# TRV_WIZ.net
KiCad netlist of a schematic drawn in EAGLE
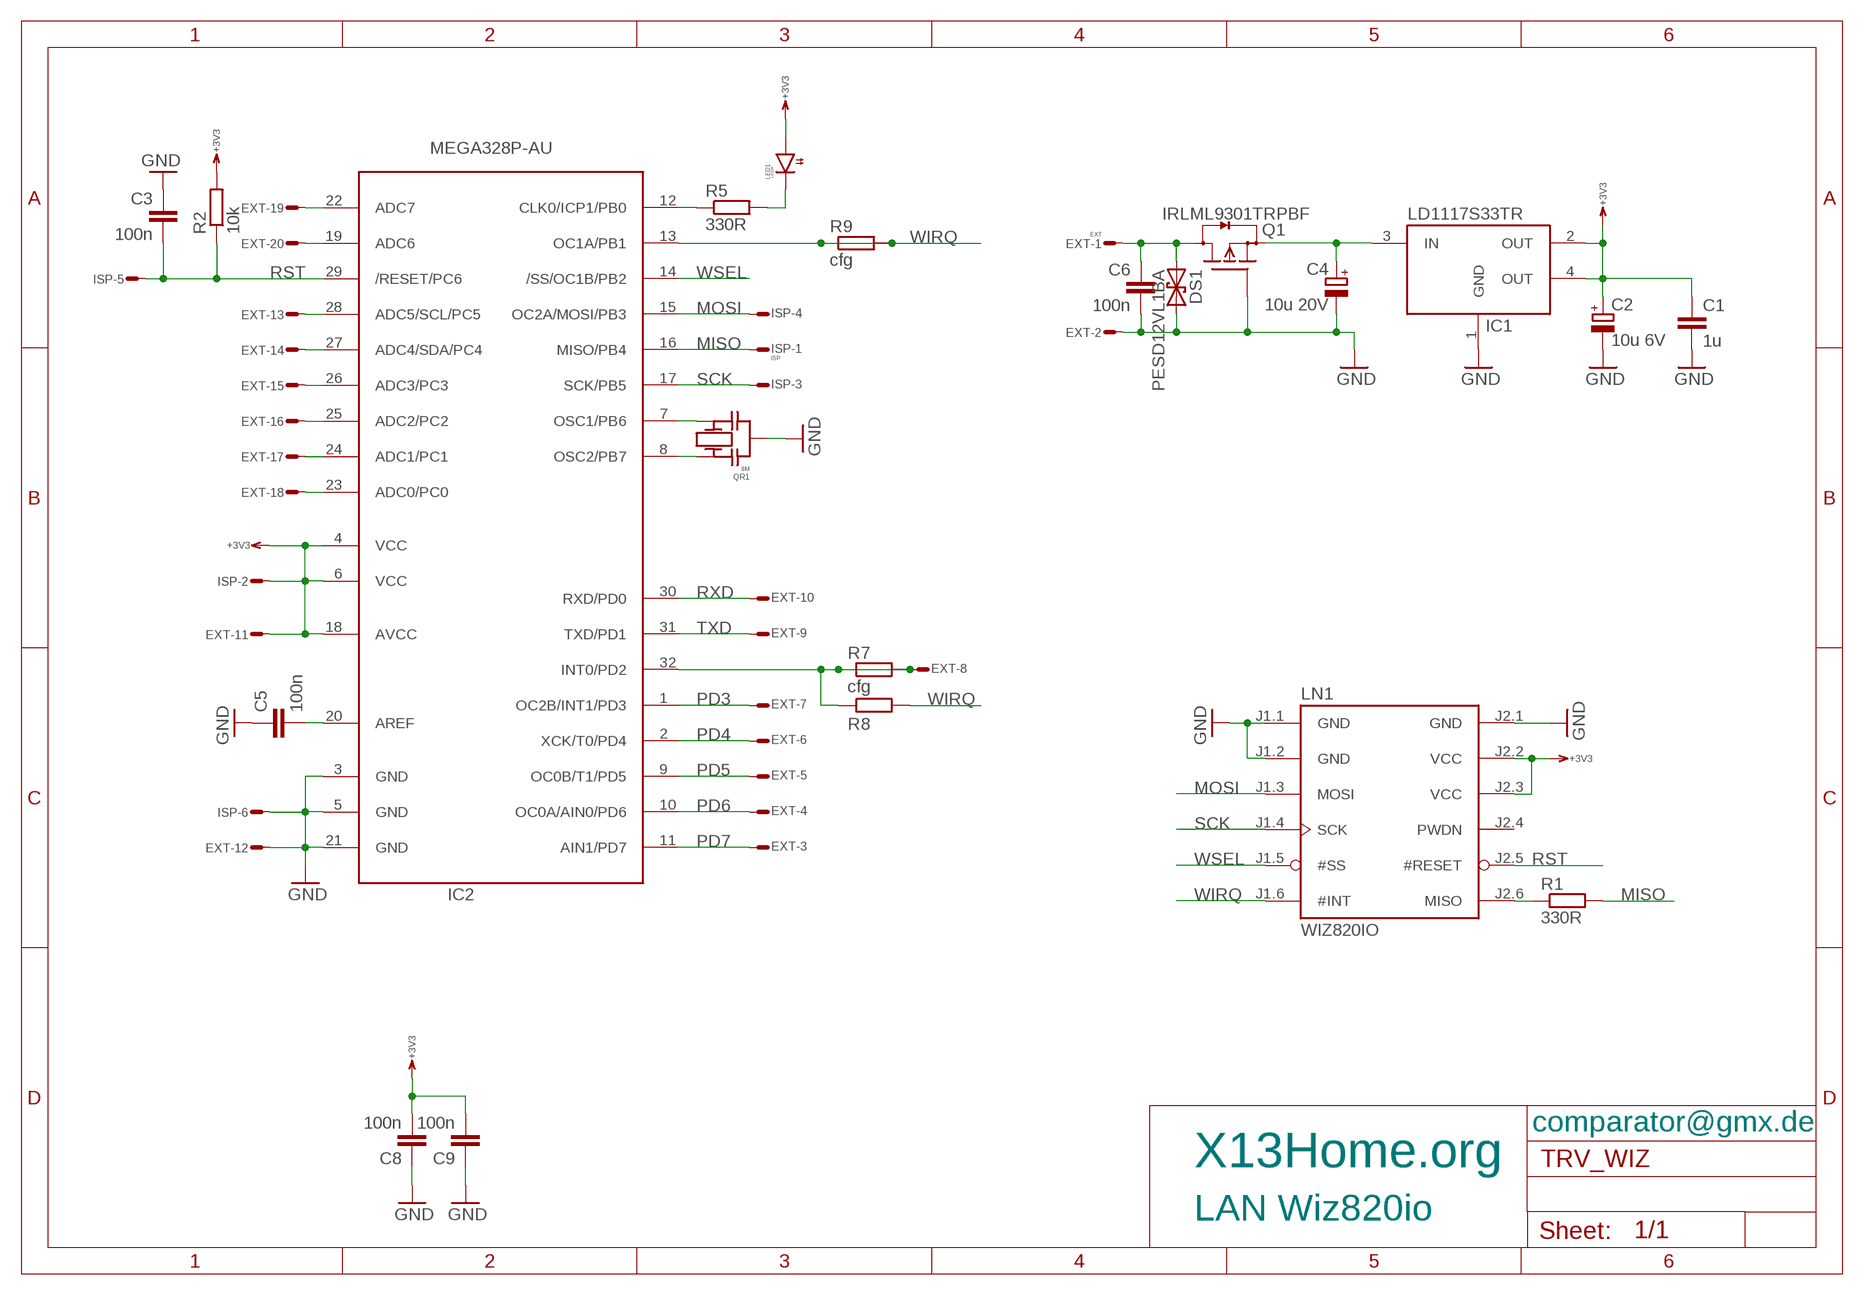
[diagram p0: schematic, sheet 1]

(export (version "E")
  (design (tool "Eeschema 10.0.6"))
  (components
    (comp (ref "C1")
      (value "1u")
      (footprint "eagle-import:0603")
      (libsource (lib "eagle-import") (part "C0603"))
    )
    (comp (ref "C2")
      (value "10u 6V")
      (footprint "eagle-import:SMC_A")
      (libsource (lib "eagle-import") (part "C_POLSMCA"))
    )
    (comp (ref "C3")
      (value "100n")
      (footprint "eagle-import:0603")
      (libsource (lib "eagle-import") (part "C0603"))
    )
    (comp (ref "C4")
      (value "10u 20V")
      (footprint "eagle-import:SMC_B")
      (libsource (lib "eagle-import") (part "C_POLSMCB"))
    )
    (comp (ref "C5")
      (value "100n")
      (footprint "eagle-import:0603")
      (libsource (lib "eagle-import") (part "C0603"))
    )
    (comp (ref "C6")
      (value "100n")
      (footprint "eagle-import:0603")
      (libsource (lib "eagle-import") (part "C0603"))
    )
    (comp (ref "C8")
      (value "100n")
      (footprint "eagle-import:0603")
      (libsource (lib "eagle-import") (part "C0603"))
    )
    (comp (ref "C9")
      (value "100n")
      (footprint "eagle-import:0603")
      (libsource (lib "eagle-import") (part "C0603"))
    )
    (comp (ref "DS1")
      (value "PESD12VL1BA")
      (footprint "eagle-import:SOD323")
      (libsource (lib "eagle-import") (part "TVS-U323"))
    )
    (comp (ref "EXT")
      (value "EXT")
      (footprint "eagle-import:ML20S")
      (libsource (lib "eagle-import") (part "ML20?ES"))
    )
    (comp (ref "IC1")
      (value "LD1117S33TR")
      (footprint "eagle-import:SOT223")
      (libsource (lib "eagle-import") (part "LDO_4P"))
    )
    (comp (ref "IC2")
      (value "MEGA328P-AU")
      (footprint "eagle-import:TQFP32-08")
      (libsource (lib "eagle-import") (part "MEGA168PA"))
    )
    (comp (ref "ISP")
      (value "ISP")
      (footprint "eagle-import:ML6S")
      (libsource (lib "eagle-import") (part "ML6ES"))
    )
    (comp (ref "LED1")
      (value "LEDR")
      (footprint "eagle-import:T1-3_4")
      (libsource (lib "eagle-import") (part "LEDT134"))
    )
    (comp (ref "LN1")
      (value "WIZ820IO")
      (footprint "eagle-import:WIZ820IO")
      (libsource (lib "eagle-import") (part "WIZ820IO"))
    )
    (comp (ref "Q1")
      (value "IRLML9301TRPBF")
      (footprint "eagle-import:SOT23")
      (libsource (lib "eagle-import") (part "FET-PDSOT23"))
    )
    (comp (ref "QR1")
      (value "8M")
      (footprint "eagle-import:CSTCE")
      (libsource (lib "eagle-import") (part "QRCE"))
    )
    (comp (ref "R1")
      (value "330R")
      (footprint "eagle-import:0603")
      (libsource (lib "eagle-import") (part "R0603"))
    )
    (comp (ref "R2")
      (value "10k")
      (footprint "eagle-import:0603")
      (libsource (lib "eagle-import") (part "R0603"))
    )
    (comp (ref "R5")
      (value "330R")
      (footprint "eagle-import:0603")
      (libsource (lib "eagle-import") (part "R0603"))
    )
    (comp (ref "R7")
      (value "cfg")
      (footprint "eagle-import:0402")
      (libsource (lib "eagle-import") (part "R0402"))
    )
    (comp (ref "R8")
      (value "cfg")
      (footprint "eagle-import:0402")
      (libsource (lib "eagle-import") (part "R0402"))
    )
    (comp (ref "R9")
      (value "cfg")
      (footprint "eagle-import:0402")
      (libsource (lib "eagle-import") (part "R0402"))
    )
  )
  (nets
    (net (code "1") (name "+3V3") (class "Default")
      (node (ref "C1") (pin "1") (pinfunction "1_1") (pintype "passive"))
      (node (ref "C2") (pin "+") (pinfunction "+_+") (pintype "passive"))
      (node (ref "C8") (pin "2") (pinfunction "2_2") (pintype "passive"))
      (node (ref "C9") (pin "2") (pinfunction "2_2") (pintype "passive"))
      (node (ref "EXT") (pin "11") (pinfunction "S_11") (pintype "passive"))
      (node (ref "IC1") (pin "2") (pinfunction "OUT_2") (pintype "bidirectional"))
      (node (ref "IC1") (pin "4") (pinfunction "OUT_4") (pintype "bidirectional"))
      (node (ref "IC2") (pin "18") (pinfunction "AVCC_18") (pintype "bidirectional"))
      (node (ref "IC2") (pin "4") (pinfunction "VCC_4") (pintype "bidirectional"))
      (node (ref "IC2") (pin "6") (pinfunction "VCC_6") (pintype "bidirectional"))
      (node (ref "ISP") (pin "2") (pinfunction "S_2") (pintype "passive"))
      (node (ref "LED1") (pin "A") (pinfunction "A_A") (pintype "bidirectional"))
      (node (ref "LN1") (pin "J2.2") (pinfunction "VCC_J2.2") (pintype "bidirectional"))
      (node (ref "LN1") (pin "J2.3") (pinfunction "VCC_J2.3") (pintype "bidirectional"))
      (node (ref "R2") (pin "2") (pinfunction "2_2") (pintype "passive"))
    )
    (net (code "2") (name "/MISO") (class "Default")
      (node (ref "IC2") (pin "16") (pinfunction "MISO/PB4_16") (pintype "bidirectional"))
      (node (ref "ISP") (pin "1") (pinfunction "S_1") (pintype "passive"))
      (node (ref "R1") (pin "2") (pinfunction "2_2") (pintype "passive"))
    )
    (net (code "3") (name "/MOSI") (class "Default")
      (node (ref "IC2") (pin "15") (pinfunction "OC2A/MOSI/PB3_15") (pintype "bidirectional"))
      (node (ref "ISP") (pin "4") (pinfunction "S_4") (pintype "passive"))
      (node (ref "LN1") (pin "J1.3") (pinfunction "MOSI_J1.3") (pintype "input"))
    )
    (net (code "4") (name "/PD3") (class "Default")
      (node (ref "EXT") (pin "7") (pinfunction "S_7") (pintype "passive"))
      (node (ref "IC2") (pin "1") (pinfunction "OC2B/INT1/PD3_1") (pintype "bidirectional"))
    )
    (net (code "5") (name "/PD4") (class "Default")
      (node (ref "EXT") (pin "6") (pinfunction "S_6") (pintype "passive"))
      (node (ref "IC2") (pin "2") (pinfunction "XCK/T0/PD4_2") (pintype "bidirectional"))
    )
    (net (code "6") (name "/PD5") (class "Default")
      (node (ref "EXT") (pin "5") (pinfunction "S_5") (pintype "passive"))
      (node (ref "IC2") (pin "9") (pinfunction "OC0B/T1/PD5_9") (pintype "bidirectional"))
    )
    (net (code "7") (name "/PD6") (class "Default")
      (node (ref "EXT") (pin "4") (pinfunction "S_4") (pintype "passive"))
      (node (ref "IC2") (pin "10") (pinfunction "OC0A/AIN0/PD6_10") (pintype "bidirectional"))
    )
    (net (code "8") (name "/PD7") (class "Default")
      (node (ref "EXT") (pin "3") (pinfunction "S_3") (pintype "passive"))
      (node (ref "IC2") (pin "11") (pinfunction "AIN1/PD7_11") (pintype "bidirectional"))
    )
    (net (code "9") (name "/RST") (class "Default")
      (node (ref "C3") (pin "2") (pinfunction "2_2") (pintype "passive"))
      (node (ref "IC2") (pin "29") (pinfunction "/RESET/PC6_29") (pintype "bidirectional"))
      (node (ref "ISP") (pin "5") (pinfunction "S_5") (pintype "passive"))
      (node (ref "LN1") (pin "J2.5") (pinfunction "#RESET_J2.5") (pintype "input"))
      (node (ref "R2") (pin "1") (pinfunction "1_1") (pintype "passive"))
    )
    (net (code "10") (name "/RXD") (class "Default")
      (node (ref "EXT") (pin "10") (pinfunction "S_10") (pintype "passive"))
      (node (ref "IC2") (pin "30") (pinfunction "RXD/PD0_30") (pintype "bidirectional"))
    )
    (net (code "11") (name "/SCK") (class "Default")
      (node (ref "IC2") (pin "17") (pinfunction "SCK/PB5_17") (pintype "bidirectional"))
      (node (ref "ISP") (pin "3") (pinfunction "S_3") (pintype "passive"))
      (node (ref "LN1") (pin "J1.4") (pinfunction "SCK_J1.4") (pintype "input"))
    )
    (net (code "12") (name "/TXD") (class "Default")
      (node (ref "EXT") (pin "9") (pinfunction "S_9") (pintype "passive"))
      (node (ref "IC2") (pin "31") (pinfunction "TXD/PD1_31") (pintype "bidirectional"))
    )
    (net (code "13") (name "/WIRQ") (class "Default")
      (node (ref "IC2") (pin "13") (pinfunction "OC1A/PB1_13") (pintype "bidirectional"))
      (node (ref "LN1") (pin "J1.6") (pinfunction "#INT_J1.6") (pintype "open_collector"))
      (node (ref "R8") (pin "2") (pinfunction "2_2") (pintype "passive"))
      (node (ref "R9") (pin "1") (pinfunction "1_1") (pintype "passive"))
      (node (ref "R9") (pin "2") (pinfunction "2_2") (pintype "passive"))
    )
    (net (code "14") (name "/WSEL") (class "Default")
      (node (ref "IC2") (pin "14") (pinfunction "/SS/OC1B/PB2_14") (pintype "bidirectional"))
      (node (ref "LN1") (pin "J1.5") (pinfunction "#SS_J1.5") (pintype "input"))
    )
    (net (code "15") (name "GND") (class "Default")
      (node (ref "C1") (pin "2") (pinfunction "2_2") (pintype "passive"))
      (node (ref "C2") (pin "-") (pinfunction "-_-") (pintype "passive"))
      (node (ref "C3") (pin "1") (pinfunction "1_1") (pintype "passive"))
      (node (ref "C4") (pin "-") (pinfunction "-_-") (pintype "passive"))
      (node (ref "C5") (pin "1") (pinfunction "1_1") (pintype "passive"))
      (node (ref "C6") (pin "2") (pinfunction "2_2") (pintype "passive"))
      (node (ref "C8") (pin "1") (pinfunction "1_1") (pintype "passive"))
      (node (ref "C9") (pin "1") (pinfunction "1_1") (pintype "passive"))
      (node (ref "DS1") (pin "C") (pinfunction "2_C") (pintype "passive"))
      (node (ref "EXT") (pin "12") (pinfunction "S_12") (pintype "passive"))
      (node (ref "EXT") (pin "2") (pinfunction "S_2") (pintype "passive"))
      (node (ref "IC1") (pin "1") (pinfunction "GND_1") (pintype "bidirectional"))
      (node (ref "IC2") (pin "21") (pinfunction "GND_21") (pintype "bidirectional"))
      (node (ref "IC2") (pin "3") (pinfunction "GND_3") (pintype "bidirectional"))
      (node (ref "IC2") (pin "5") (pinfunction "GND_5") (pintype "bidirectional"))
      (node (ref "ISP") (pin "6") (pinfunction "S_6") (pintype "passive"))
      (node (ref "LN1") (pin "J1.1") (pinfunction "GND_J1.1") (pintype "bidirectional"))
      (node (ref "LN1") (pin "J1.2") (pinfunction "GND_J1.2") (pintype "bidirectional"))
      (node (ref "LN1") (pin "J2.1") (pinfunction "GND_J2.1") (pintype "bidirectional"))
      (node (ref "Q1") (pin "1") (pinfunction "G_1") (pintype "passive"))
      (node (ref "QR1") (pin "G") (pinfunction "M_G") (pintype "passive"))
    )
    (net (code "16") (name "Net-(DS1-1)") (class "Default")
      (node (ref "C6") (pin "1") (pinfunction "1_1") (pintype "passive"))
      (node (ref "DS1") (pin "A") (pinfunction "1_A") (pintype "passive"))
      (node (ref "EXT") (pin "1") (pinfunction "S_1") (pintype "passive"))
      (node (ref "Q1") (pin "3") (pinfunction "D_3") (pintype "passive"))
    )
    (net (code "17") (name "Net-(EXTE-S)") (class "Default")
      (node (ref "EXT") (pin "13") (pinfunction "S_13") (pintype "passive"))
      (node (ref "IC2") (pin "28") (pinfunction "ADC5/SCL/PC5_28") (pintype "bidirectional"))
    )
    (net (code "18") (name "Net-(EXTF-S)") (class "Default")
      (node (ref "EXT") (pin "14") (pinfunction "S_14") (pintype "passive"))
      (node (ref "IC2") (pin "27") (pinfunction "ADC4/SDA/PC4_27") (pintype "bidirectional"))
    )
    (net (code "19") (name "Net-(EXTG-S)") (class "Default")
      (node (ref "EXT") (pin "15") (pinfunction "S_15") (pintype "passive"))
      (node (ref "IC2") (pin "26") (pinfunction "ADC3/PC3_26") (pintype "bidirectional"))
    )
    (net (code "20") (name "Net-(EXTH-S)") (class "Default")
      (node (ref "EXT") (pin "16") (pinfunction "S_16") (pintype "passive"))
      (node (ref "IC2") (pin "25") (pinfunction "ADC2/PC2_25") (pintype "bidirectional"))
    )
    (net (code "21") (name "Net-(EXTI-S)") (class "Default")
      (node (ref "EXT") (pin "17") (pinfunction "S_17") (pintype "passive"))
      (node (ref "IC2") (pin "24") (pinfunction "ADC1/PC1_24") (pintype "bidirectional"))
    )
    (net (code "22") (name "Net-(EXTJ-S)") (class "Default")
      (node (ref "EXT") (pin "18") (pinfunction "S_18") (pintype "passive"))
      (node (ref "IC2") (pin "23") (pinfunction "ADC0/PC0_23") (pintype "bidirectional"))
    )
    (net (code "23") (name "Net-(EXTK-S)") (class "Default")
      (node (ref "EXT") (pin "19") (pinfunction "S_19") (pintype "passive"))
      (node (ref "IC2") (pin "22") (pinfunction "ADC7_22") (pintype "bidirectional"))
    )
    (net (code "24") (name "Net-(EXTM-S)") (class "Default")
      (node (ref "EXT") (pin "20") (pinfunction "S_20") (pintype "passive"))
      (node (ref "IC2") (pin "19") (pinfunction "ADC6_19") (pintype "bidirectional"))
    )
    (net (code "25") (name "Net-(EXTS-S)") (class "Default")
      (node (ref "EXT") (pin "8") (pinfunction "S_8") (pintype "passive"))
      (node (ref "IC2") (pin "32") (pinfunction "INT0/PD2_32") (pintype "bidirectional"))
      (node (ref "R7") (pin "1") (pinfunction "1_1") (pintype "passive"))
      (node (ref "R7") (pin "2") (pinfunction "2_2") (pintype "passive"))
      (node (ref "R8") (pin "1") (pinfunction "1_1") (pintype "passive"))
    )
    (net (code "26") (name "Net-(IC1-IN)") (class "Default")
      (node (ref "C4") (pin "+") (pinfunction "+_+") (pintype "passive"))
      (node (ref "IC1") (pin "3") (pinfunction "IN_3") (pintype "bidirectional"))
      (node (ref "Q1") (pin "2") (pinfunction "S_2") (pintype "passive"))
    )
    (net (code "27") (name "Net-(IC2-AREF)") (class "Default")
      (node (ref "C5") (pin "2") (pinfunction "2_2") (pintype "passive"))
      (node (ref "IC2") (pin "20") (pinfunction "AREF_20") (pintype "bidirectional"))
    )
    (net (code "28") (name "Net-(IC2-CLK0{slash}ICP1{slash}PB0)") (class "Default")
      (node (ref "IC2") (pin "12") (pinfunction "CLK0/ICP1/PB0_12") (pintype "bidirectional"))
      (node (ref "R5") (pin "1") (pinfunction "1_1") (pintype "passive"))
    )
    (net (code "29") (name "Net-(IC2-OSC1{slash}PB6)") (class "Default")
      (node (ref "IC2") (pin "7") (pinfunction "OSC1/PB6_7") (pintype "bidirectional"))
      (node (ref "QR1") (pin "B") (pinfunction "2_B") (pintype "passive"))
    )
    (net (code "30") (name "Net-(IC2-OSC2{slash}PB7)") (class "Default")
      (node (ref "IC2") (pin "8") (pinfunction "OSC2/PB7_8") (pintype "bidirectional"))
      (node (ref "QR1") (pin "A") (pinfunction "1_A") (pintype "passive"))
    )
    (net (code "31") (name "Net-(LED1-PadC)") (class "Default")
      (node (ref "LED1") (pin "C") (pinfunction "C_C") (pintype "bidirectional"))
      (node (ref "R5") (pin "2") (pinfunction "2_2") (pintype "passive"))
    )
    (net (code "32") (name "Net-(LN1-MISO)") (class "Default")
      (node (ref "LN1") (pin "J2.6") (pinfunction "MISO_J2.6") (pintype "output"))
      (node (ref "R1") (pin "1") (pinfunction "1_1") (pintype "passive"))
    )
    (net (code "33") (name "unconnected-(LN1-PWDN-PadJ2.4)") (class "Default")
      (node (ref "LN1") (pin "J2.4") (pinfunction "PWDN_J2.4") (pintype "input"))
    )
  )
)
